# SAI.net
KiCad netlist of a schematic drawn in Altium Designer
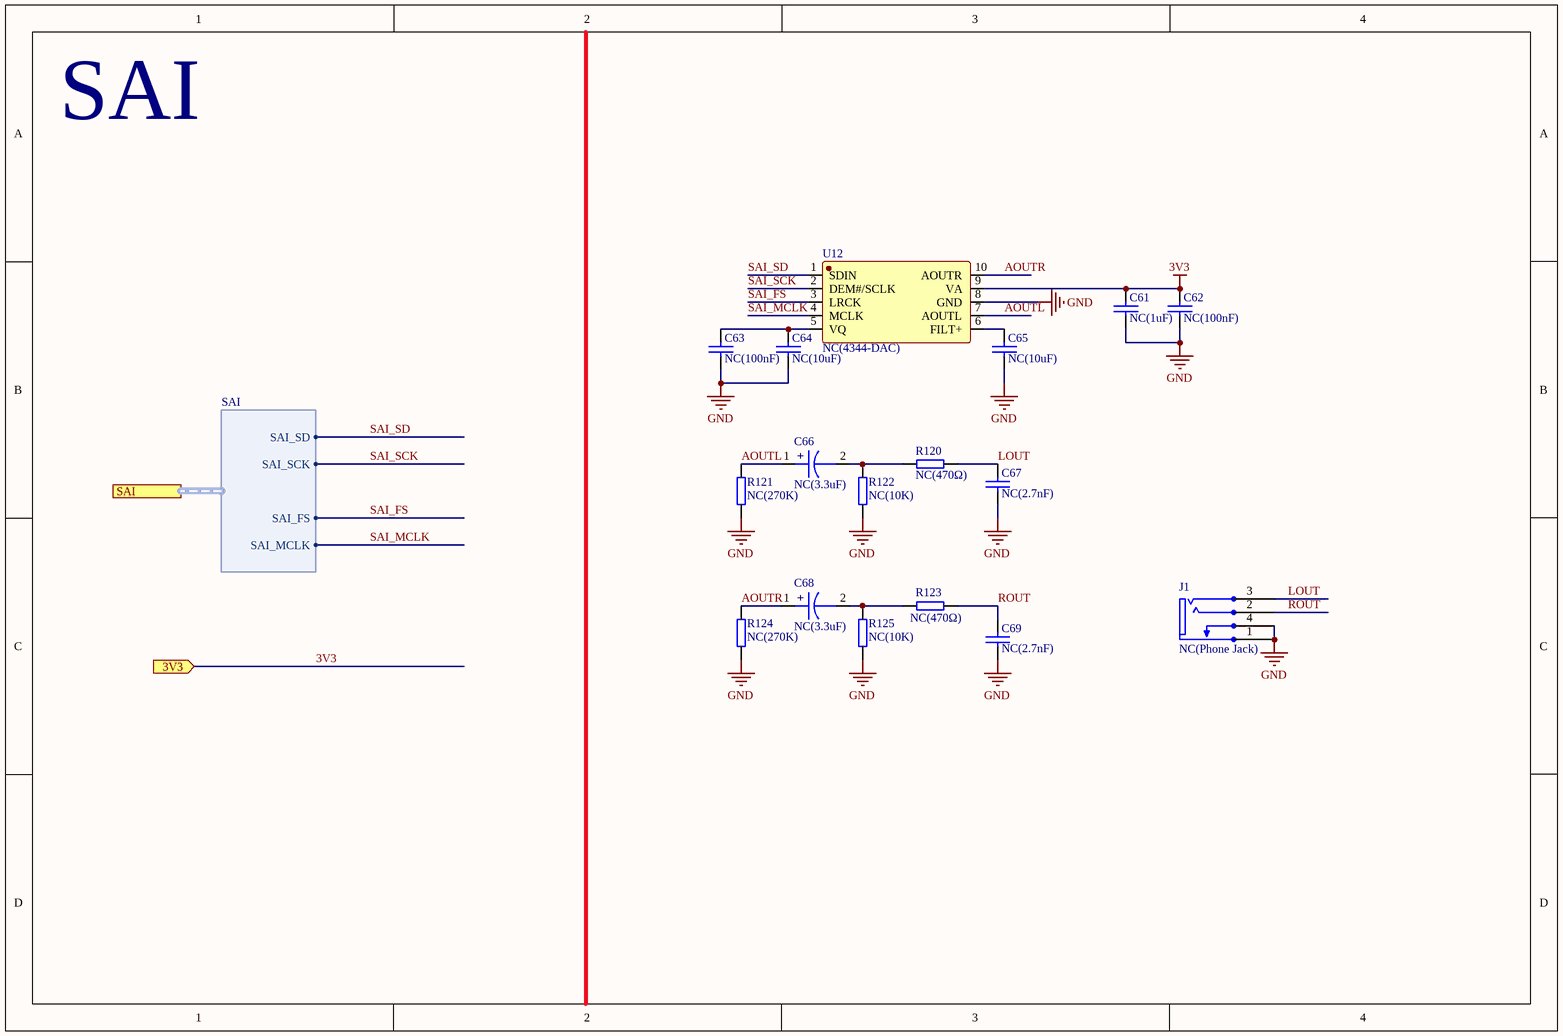
[diagram p0: SAI.SchDoc]

(export (version "E")
  (design (tool "Eeschema 10.0.6"))
  (components
    (comp (ref "C61")
      (value "NC(1uF)")
      (footprint "0402_C")
      (description "Capacitor")
      (libsource (lib "*") (part "CAP"))
    )
    (comp (ref "C62")
      (value "NC(100nF)")
      (footprint "0402_C")
      (description "Capacitor")
      (libsource (lib "*") (part "CAP"))
    )
    (comp (ref "C63")
      (value "NC(100nF)")
      (footprint "0402_C")
      (description "Capacitor")
      (libsource (lib "*") (part "CAP"))
    )
    (comp (ref "C64")
      (value "NC(10uF)")
      (footprint "0603_C")
      (description "Capacitor")
      (libsource (lib "*") (part "CAP"))
    )
    (comp (ref "C65")
      (value "NC(10uF)")
      (footprint "0603_C")
      (description "Capacitor")
      (libsource (lib "*") (part "CAP"))
    )
    (comp (ref "C66")
      (value "NC(3.3uF)")
      (footprint "CAP-TH_BD5.0-P2.00-D0.8-FD")
      (description "3.3uF")
      (libsource (lib "wch_sch_others") (part "CAPACITOR POL"))
    )
    (comp (ref "C67")
      (value "NC(2.7nF)")
      (footprint "0402_C")
      (description "Capacitor")
      (libsource (lib "*") (part "CAP"))
    )
    (comp (ref "C68")
      (value "NC(3.3uF)")
      (footprint "CAP-TH_BD5.0-P2.00-D0.8-FD")
      (description "3.3uF")
      (libsource (lib "wch_sch_others") (part "CAPACITOR POL"))
    )
    (comp (ref "C69")
      (value "NC(2.7nF)")
      (footprint "0402_C")
      (description "Capacitor")
      (libsource (lib "*") (part "CAP"))
    )
    (comp (ref "J1")
      (value "NC(Phone Jack)")
      (footprint "3.5MMEARPHONE")
      (libsource (lib "wch_sch_others") (part "Phone Jack"))
    )
    (comp (ref "R120") (value "NC(470Ω)") (footprint "0402") (libsource (lib "*") (part "RES")))
    (comp (ref "R121") (value "NC(270K)") (footprint "0402") (libsource (lib "*") (part "RES")))
    (comp (ref "R122") (value "NC(10K)") (footprint "0402") (libsource (lib "*") (part "RES")))
    (comp (ref "R123") (value "NC(470Ω)") (footprint "0402") (libsource (lib "*") (part "RES")))
    (comp (ref "R124") (value "NC(270K)") (footprint "0402") (libsource (lib "*") (part "RES")))
    (comp (ref "R125") (value "NC(10K)") (footprint "0402") (libsource (lib "*") (part "RES")))
    (comp (ref "U12")
      (value "NC(4344-DAC)")
      (footprint "TSSOP-10_L3.0-W3.0-P0.50-LS4.9-BL")
      (libsource (lib "wch_sch_others") (part "CS4344-CZZ"))
    )
  )
  (nets
    (net (code "2") (name "/AOUTL") (class "Default")
      (node (ref "C66") (pin "1") (pinfunction "1_1") (pintype "passive"))
      (node (ref "R121") (pin "1") (pintype "passive"))
      (node (ref "U12") (pin "7") (pinfunction "AOUTL_7") (pintype "passive"))
    )
    (net (code "3") (name "/AOUTR") (class "Default")
      (node (ref "C68") (pin "1") (pinfunction "1_1") (pintype "passive"))
      (node (ref "R124") (pin "1") (pintype "passive"))
      (node (ref "U12") (pin "10") (pinfunction "AOUTR_10") (pintype "passive"))
    )
    (net (code "4") (name "/LOUT") (class "Default")
      (node (ref "C67") (pin "2") (pinfunction "2_2") (pintype "passive"))
      (node (ref "J1") (pin "3") (pintype "passive"))
      (node (ref "R120") (pin "2") (pintype "passive"))
    )
    (net (code "5") (name "/ROUT") (class "Default")
      (node (ref "C69") (pin "2") (pinfunction "2_2") (pintype "passive"))
      (node (ref "J1") (pin "2") (pintype "passive"))
      (node (ref "R123") (pin "2") (pintype "passive"))
    )
    (net (code "6") (name "/SAI_FS") (class "Default")
      (node (ref "U12") (pin "3") (pinfunction "LRCK_3") (pintype "passive"))
    )
    (net (code "7") (name "/SAI_MCLK") (class "Default")
      (node (ref "U12") (pin "4") (pinfunction "MCLK_4") (pintype "passive"))
    )
    (net (code "8") (name "/SAI_SCK") (class "Default")
      (node (ref "U12") (pin "2") (pinfunction "DEM#/SCLK_2") (pintype "passive"))
    )
    (net (code "9") (name "/SAI_SD") (class "Default")
      (node (ref "U12") (pin "1") (pinfunction "SDIN_1") (pintype "passive"))
    )
    (net (code "11") (name "3V3") (class "Default")
      (node (ref "C61") (pin "2") (pinfunction "2_2") (pintype "passive"))
      (node (ref "C62") (pin "2") (pinfunction "2_2") (pintype "passive"))
      (node (ref "U12") (pin "9") (pinfunction "VA_9") (pintype "passive"))
    )
    (net (code "12") (name "GND") (class "Default")
      (node (ref "C61") (pin "1") (pinfunction "1_1") (pintype "passive"))
      (node (ref "C62") (pin "1") (pinfunction "1_1") (pintype "passive"))
      (node (ref "C63") (pin "1") (pinfunction "1_1") (pintype "passive"))
      (node (ref "C64") (pin "1") (pinfunction "1_1") (pintype "passive"))
      (node (ref "C65") (pin "1") (pinfunction "1_1") (pintype "passive"))
      (node (ref "C67") (pin "1") (pinfunction "1_1") (pintype "passive"))
      (node (ref "C69") (pin "1") (pinfunction "1_1") (pintype "passive"))
      (node (ref "J1") (pin "1") (pintype "passive"))
      (node (ref "J1") (pin "4") (pintype "passive"))
      (node (ref "R121") (pin "2") (pintype "passive"))
      (node (ref "R122") (pin "2") (pintype "passive"))
      (node (ref "R124") (pin "2") (pintype "passive"))
      (node (ref "R125") (pin "2") (pintype "passive"))
      (node (ref "U12") (pin "8") (pinfunction "GND_8") (pintype "passive"))
    )
    (net (code "13") (name "Net-(C66-Pad2)") (class "Default")
      (node (ref "C66") (pin "2") (pinfunction "2_2") (pintype "passive"))
      (node (ref "R120") (pin "1") (pintype "passive"))
      (node (ref "R122") (pin "1") (pintype "passive"))
    )
    (net (code "14") (name "Net-(C68-Pad2)") (class "Default")
      (node (ref "C68") (pin "2") (pinfunction "2_2") (pintype "passive"))
      (node (ref "R123") (pin "1") (pintype "passive"))
      (node (ref "R125") (pin "1") (pintype "passive"))
    )
    (net (code "15") (name "Net-(U12-FILT+)") (class "Default")
      (node (ref "C65") (pin "2") (pinfunction "2_2") (pintype "passive"))
      (node (ref "U12") (pin "6") (pinfunction "FILT+_6") (pintype "passive"))
    )
    (net (code "16") (name "Net-(U12-VQ)") (class "Default")
      (node (ref "C63") (pin "2") (pinfunction "2_2") (pintype "passive"))
      (node (ref "C64") (pin "2") (pinfunction "2_2") (pintype "passive"))
      (node (ref "U12") (pin "5") (pinfunction "VQ_5") (pintype "passive"))
    )
  )
)
